# Sheet1.net
KiCad netlist of a schematic drawn in Altium Designer
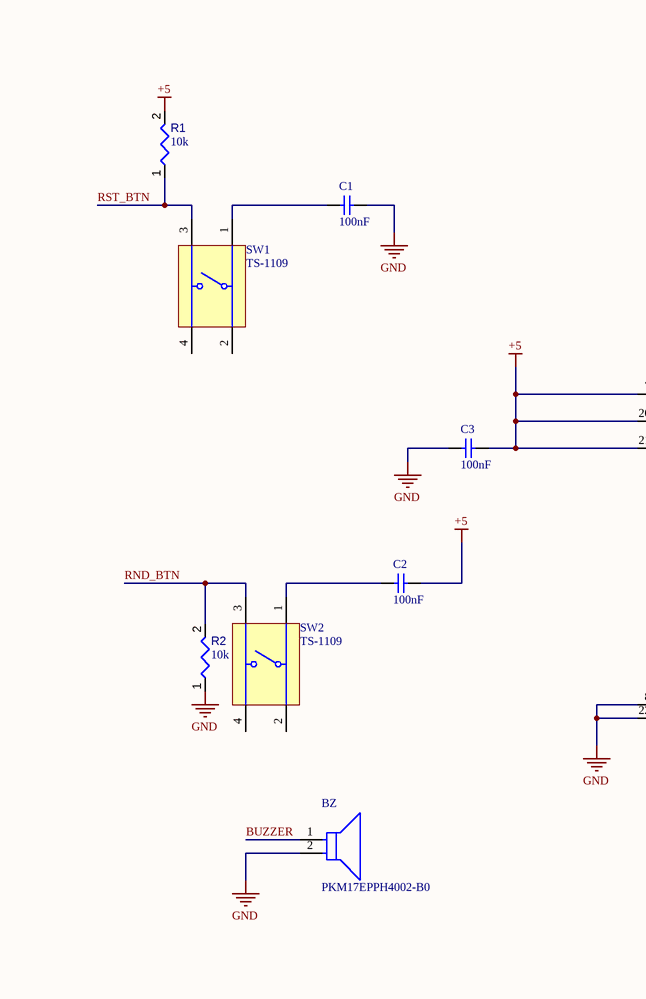
[diagram p0: Sheet1.SchDoc, left]
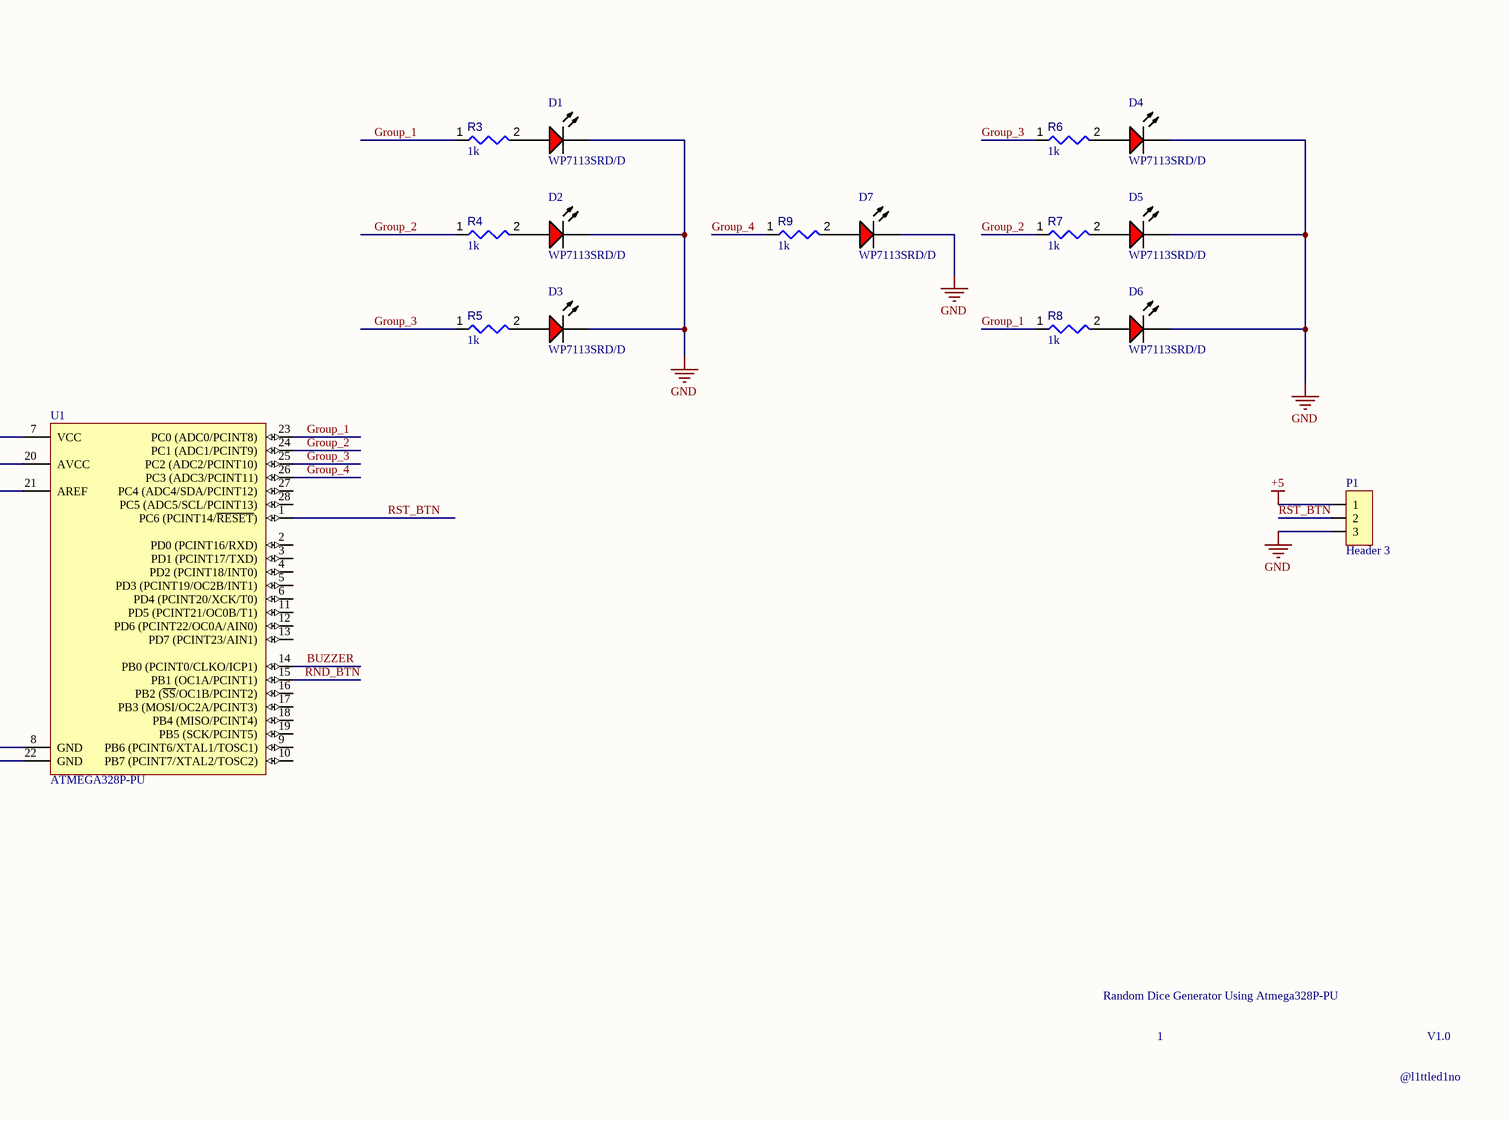
[diagram p1: Sheet1.SchDoc, right]

(export (version "E")
  (design (tool "Eeschema 10.0.6"))
  (components
    (comp (ref "BZ")
      (value "PKM17EPPH4002-B0")
      (footprint "FP-PKM17EPPH4002-B0-MFG")
      (description "AUDIO PIEZO TRANSDUCER 25V TH")
      (libsource (lib "Altium Content Vault") (part "5f581d31613f872430949aa526fd155"))
    )
    (comp (ref "C1")
      (value "100nF")
      (footprint "CAP Ceramic/W200")
      (description "Capacitor non-pol")
      (libsource (lib "chipfc_libs") (part "Capacitor NP"))
    )
    (comp (ref "C2")
      (value "100nF")
      (footprint "CAP Ceramic/W200")
      (description "Capacitor non-pol")
      (libsource (lib "chipfc_libs") (part "Capacitor NP"))
    )
    (comp (ref "C3")
      (value "100nF")
      (footprint "CAP Ceramic/W200")
      (description "Capacitor non-pol")
      (libsource (lib "chipfc_libs") (part "Capacitor NP"))
    )
    (comp (ref "D1")
      (value "WP7113SRD/D")
      (footprint "KING-WP7113SRDD_V")
      (description "The Super Bright Red Source Color Device, 1.85 V, -40 to 85 degC, 2-Pin THD, RoHS, Tape and Reel")
      (fields (field (name "MANUFACTURER") "Kingbright"))
      (libsource (lib "l1ttled1no") (part "LED-RED-AK-2"))
    )
    (comp (ref "D2")
      (value "WP7113SRD/D")
      (footprint "KING-WP7113SRDD_V")
      (description "The Super Bright Red Source Color Device, 1.85 V, -40 to 85 degC, 2-Pin THD, RoHS, Tape and Reel")
      (fields (field (name "MANUFACTURER") "Kingbright"))
      (libsource (lib "l1ttled1no") (part "LED-RED-AK-2"))
    )
    (comp (ref "D3")
      (value "WP7113SRD/D")
      (footprint "KING-WP7113SRDD_V")
      (description "The Super Bright Red Source Color Device, 1.85 V, -40 to 85 degC, 2-Pin THD, RoHS, Tape and Reel")
      (fields (field (name "MANUFACTURER") "Kingbright"))
      (libsource (lib "l1ttled1no") (part "LED-RED-AK-2"))
    )
    (comp (ref "D4")
      (value "WP7113SRD/D")
      (footprint "KING-WP7113SRDD_V")
      (description "The Super Bright Red Source Color Device, 1.85 V, -40 to 85 degC, 2-Pin THD, RoHS, Tape and Reel")
      (fields (field (name "MANUFACTURER") "Kingbright"))
      (libsource (lib "l1ttled1no") (part "LED-RED-AK-2"))
    )
    (comp (ref "D5")
      (value "WP7113SRD/D")
      (footprint "KING-WP7113SRDD_V")
      (description "The Super Bright Red Source Color Device, 1.85 V, -40 to 85 degC, 2-Pin THD, RoHS, Tape and Reel")
      (fields (field (name "MANUFACTURER") "Kingbright"))
      (libsource (lib "l1ttled1no") (part "LED-RED-AK-2"))
    )
    (comp (ref "D6")
      (value "WP7113SRD/D")
      (footprint "KING-WP7113SRDD_V")
      (description "The Super Bright Red Source Color Device, 1.85 V, -40 to 85 degC, 2-Pin THD, RoHS, Tape and Reel")
      (fields (field (name "MANUFACTURER") "Kingbright"))
      (libsource (lib "l1ttled1no") (part "LED-RED-AK-2"))
    )
    (comp (ref "D7")
      (value "WP7113SRD/D")
      (footprint "KING-WP7113SRDD_V")
      (description "The Super Bright Red Source Color Device, 1.85 V, -40 to 85 degC, 2-Pin THD, RoHS, Tape and Reel")
      (fields (field (name "MANUFACTURER") "Kingbright"))
      (libsource (lib "l1ttled1no") (part "LED-RED-AK-2"))
    )
    (comp (ref "P1")
      (value "Header 3")
      (footprint "HDR/Header/3/c1")
      (description "Header, 3-Pin")
      (libsource (lib "connectors") (part "Header 3"))
    )
    (comp (ref "R1")
      (value "10k")
      (footprint "RESA60-630X240")
      (description "Axial Resistor, 10 KOhm, +/- 1%, 0.25 W, -55 to 155 degC, 2-Pin THD, RoHS, Bulk")
      (fields (field (name "TOLERANCE") "1%") (field (name "POWER") "250mW"))
      (libsource (lib "l1ttled1no") (part "RES-2"))
    )
    (comp (ref "R2")
      (value "10k")
      (footprint "RESA60-630X240")
      (description "Axial Resistor, 10 KOhm, +/- 1%, 0.25 W, -55 to 155 degC, 2-Pin THD, RoHS, Bulk")
      (fields (field (name "TOLERANCE") "1%") (field (name "POWER") "250mW"))
      (libsource (lib "l1ttled1no") (part "RES-2"))
    )
    (comp (ref "R3")
      (value "1k")
      (footprint "RESA60-630X240")
      (description "Axial Resistor, 1 KOhm, +/- 1%, 250 mW, -55 to 155 degC, 2-Pin THD, RoHS, Bulk")
      (fields (field (name "TOLERANCE") "1%") (field (name "POWER") "250mW"))
      (libsource (lib "l1ttled1no") (part "RES-2"))
    )
    (comp (ref "R4")
      (value "1k")
      (footprint "RESA60-630X240")
      (description "Axial Resistor, 1 KOhm, +/- 1%, 250 mW, -55 to 155 degC, 2-Pin THD, RoHS, Bulk")
      (fields (field (name "TOLERANCE") "1%") (field (name "POWER") "250mW"))
      (libsource (lib "l1ttled1no") (part "RES-2"))
    )
    (comp (ref "R5")
      (value "1k")
      (footprint "RESA60-630X240")
      (description "Axial Resistor, 1 KOhm, +/- 1%, 250 mW, -55 to 155 degC, 2-Pin THD, RoHS, Bulk")
      (fields (field (name "TOLERANCE") "1%") (field (name "POWER") "250mW"))
      (libsource (lib "l1ttled1no") (part "RES-2"))
    )
    (comp (ref "R6")
      (value "1k")
      (footprint "RESA60-630X240")
      (description "Axial Resistor, 1 KOhm, +/- 1%, 250 mW, -55 to 155 degC, 2-Pin THD, RoHS, Bulk")
      (fields (field (name "TOLERANCE") "1%") (field (name "POWER") "250mW"))
      (libsource (lib "l1ttled1no") (part "RES-2"))
    )
    (comp (ref "R7")
      (value "1k")
      (footprint "RESA60-630X240")
      (description "Axial Resistor, 1 KOhm, +/- 1%, 250 mW, -55 to 155 degC, 2-Pin THD, RoHS, Bulk")
      (fields (field (name "TOLERANCE") "1%") (field (name "POWER") "250mW"))
      (libsource (lib "l1ttled1no") (part "RES-2"))
    )
    (comp (ref "R8")
      (value "1k")
      (footprint "RESA60-630X240")
      (description "Axial Resistor, 1 KOhm, +/- 1%, 250 mW, -55 to 155 degC, 2-Pin THD, RoHS, Bulk")
      (fields (field (name "TOLERANCE") "1%") (field (name "POWER") "250mW"))
      (libsource (lib "l1ttled1no") (part "RES-2"))
    )
    (comp (ref "R9")
      (value "1k")
      (footprint "RESA60-630X240")
      (description "Axial Resistor, 1 KOhm, +/- 1%, 250 mW, -55 to 155 degC, 2-Pin THD, RoHS, Bulk")
      (fields (field (name "TOLERANCE") "1%") (field (name "POWER") "250mW"))
      (libsource (lib "l1ttled1no") (part "RES-2"))
    )
    (comp (ref "SW1")
      (value "TS-1109")
      (footprint "BEST-TS-1109_V")
      (description "Tactile Switch, SPST, 12 V, 50 mA, -20 to 80 degC, 4-Pin THD")
      (fields (field (name "MANUFACTURER") "Shenzhen Best"))
      (libsource (lib "l1ttled1no") (part "SW-SPST-4_A"))
    )
    (comp (ref "SW2")
      (value "TS-1109")
      (footprint "BEST-TS-1109_V")
      (description "Tactile Switch, SPST, 12 V, 50 mA, -20 to 80 degC, 4-Pin THD")
      (fields (field (name "MANUFACTURER") "Shenzhen Best"))
      (libsource (lib "l1ttled1no") (part "SW-SPST-4_A"))
    )
    (comp (ref "U1")
      (value "ATMEGA328P-PU")
      (footprint "ATML-28P3")
      (fields (field (name "MANUFACTURER") "Atmel"))
      (libsource (lib "l1ttled1no") (part "MC-8B-ATM48-IL28"))
    )
  )
  (nets
    (net (code "1") (name "+5") (class "Default")
      (node (ref "C2") (pin "2") (pinfunction "2_2") (pintype "passive"))
      (node (ref "C3") (pin "2") (pinfunction "2_2") (pintype "passive"))
      (node (ref "P1") (pin "1") (pinfunction "1_1") (pintype "passive"))
      (node (ref "R1") (pin "2") (pinfunction "2_2") (pintype "passive"))
      (node (ref "U1") (pin "20") (pinfunction "AVCC_20") (pintype "power_in"))
      (node (ref "U1") (pin "21") (pinfunction "AREF_21") (pintype "power_in"))
      (node (ref "U1") (pin "7") (pinfunction "VCC_7") (pintype "power_in"))
    )
    (net (code "2") (name "/BUZZER") (class "Default")
      (node (ref "BZ") (pin "1") (pinfunction "1_1") (pintype "passive"))
      (node (ref "U1") (pin "14") (pinfunction "PB0_(PCINT0/CLKO/ICP1)_14") (pintype "bidirectional"))
    )
    (net (code "3") (name "/Group_1") (class "Default")
      (node (ref "R3") (pin "1") (pinfunction "1_1") (pintype "passive"))
      (node (ref "R8") (pin "1") (pinfunction "1_1") (pintype "passive"))
      (node (ref "U1") (pin "23") (pinfunction "PC0_(ADC0/PCINT8)_23") (pintype "bidirectional"))
    )
    (net (code "4") (name "/Group_2") (class "Default")
      (node (ref "R4") (pin "1") (pinfunction "1_1") (pintype "passive"))
      (node (ref "R7") (pin "1") (pinfunction "1_1") (pintype "passive"))
      (node (ref "U1") (pin "24") (pinfunction "PC1_(ADC1/PCINT9)_24") (pintype "bidirectional"))
    )
    (net (code "5") (name "/Group_3") (class "Default")
      (node (ref "R5") (pin "1") (pinfunction "1_1") (pintype "passive"))
      (node (ref "R6") (pin "1") (pinfunction "1_1") (pintype "passive"))
      (node (ref "U1") (pin "25") (pinfunction "PC2_(ADC2/PCINT10)_25") (pintype "bidirectional"))
    )
    (net (code "6") (name "/Group_4") (class "Default")
      (node (ref "R9") (pin "1") (pinfunction "1_1") (pintype "passive"))
      (node (ref "U1") (pin "26") (pinfunction "PC3_(ADC3/PCINT11)_26") (pintype "bidirectional"))
    )
    (net (code "7") (name "/RND_BTN") (class "Default")
      (node (ref "R2") (pin "2") (pinfunction "2_2") (pintype "passive"))
      (node (ref "SW2") (pin "3") (pinfunction "3_3") (pintype "passive"))
      (node (ref "U1") (pin "15") (pinfunction "PB1_(OC1A/PCINT1)_15") (pintype "bidirectional"))
    )
    (net (code "8") (name "/RST_BTN") (class "Default")
      (node (ref "P1") (pin "2") (pinfunction "2_2") (pintype "passive"))
      (node (ref "R1") (pin "1") (pinfunction "1_1") (pintype "passive"))
      (node (ref "SW1") (pin "3") (pinfunction "3_3") (pintype "passive"))
      (node (ref "U1") (pin "1") (pinfunction "PC6_(PCINT14/~{RESET})_1") (pintype "bidirectional"))
    )
    (net (code "9") (name "GND") (class "Default")
      (node (ref "BZ") (pin "2") (pinfunction "2_2") (pintype "passive"))
      (node (ref "C1") (pin "2") (pinfunction "2_2") (pintype "passive"))
      (node (ref "C3") (pin "1") (pinfunction "1_1") (pintype "passive"))
      (node (ref "D1") (pin "2") (pinfunction "K_2") (pintype "passive"))
      (node (ref "D2") (pin "2") (pinfunction "K_2") (pintype "passive"))
      (node (ref "D3") (pin "2") (pinfunction "K_2") (pintype "passive"))
      (node (ref "D4") (pin "2") (pinfunction "K_2") (pintype "passive"))
      (node (ref "D5") (pin "2") (pinfunction "K_2") (pintype "passive"))
      (node (ref "D6") (pin "2") (pinfunction "K_2") (pintype "passive"))
      (node (ref "D7") (pin "2") (pinfunction "K_2") (pintype "passive"))
      (node (ref "P1") (pin "3") (pinfunction "3_3") (pintype "passive"))
      (node (ref "R2") (pin "1") (pinfunction "1_1") (pintype "passive"))
      (node (ref "U1") (pin "22") (pinfunction "GND_22") (pintype "power_in"))
      (node (ref "U1") (pin "8") (pinfunction "GND_8") (pintype "power_in"))
    )
    (net (code "10") (name "Net-(C1-Pad1)") (class "Default")
      (node (ref "C1") (pin "1") (pinfunction "1_1") (pintype "passive"))
      (node (ref "SW1") (pin "1") (pinfunction "1_1") (pintype "passive"))
    )
    (net (code "11") (name "Net-(C2-Pad1)") (class "Default")
      (node (ref "C2") (pin "1") (pinfunction "1_1") (pintype "passive"))
      (node (ref "SW2") (pin "1") (pinfunction "1_1") (pintype "passive"))
    )
    (net (code "12") (name "Net-(D1-A)") (class "Default")
      (node (ref "D1") (pin "1") (pinfunction "A_1") (pintype "passive"))
      (node (ref "R3") (pin "2") (pinfunction "2_2") (pintype "passive"))
    )
    (net (code "13") (name "Net-(D2-A)") (class "Default")
      (node (ref "D2") (pin "1") (pinfunction "A_1") (pintype "passive"))
      (node (ref "R4") (pin "2") (pinfunction "2_2") (pintype "passive"))
    )
    (net (code "14") (name "Net-(D3-A)") (class "Default")
      (node (ref "D3") (pin "1") (pinfunction "A_1") (pintype "passive"))
      (node (ref "R5") (pin "2") (pinfunction "2_2") (pintype "passive"))
    )
    (net (code "15") (name "Net-(D4-A)") (class "Default")
      (node (ref "D4") (pin "1") (pinfunction "A_1") (pintype "passive"))
      (node (ref "R6") (pin "2") (pinfunction "2_2") (pintype "passive"))
    )
    (net (code "16") (name "Net-(D5-A)") (class "Default")
      (node (ref "D5") (pin "1") (pinfunction "A_1") (pintype "passive"))
      (node (ref "R7") (pin "2") (pinfunction "2_2") (pintype "passive"))
    )
    (net (code "17") (name "Net-(D6-A)") (class "Default")
      (node (ref "D6") (pin "1") (pinfunction "A_1") (pintype "passive"))
      (node (ref "R8") (pin "2") (pinfunction "2_2") (pintype "passive"))
    )
    (net (code "18") (name "Net-(D7-A)") (class "Default")
      (node (ref "D7") (pin "1") (pinfunction "A_1") (pintype "passive"))
      (node (ref "R9") (pin "2") (pinfunction "2_2") (pintype "passive"))
    )
    (net (code "19") (name "unconnected-(SW1-Pad2)") (class "Default")
      (node (ref "SW1") (pin "2") (pinfunction "2_2") (pintype "passive"))
    )
    (net (code "20") (name "unconnected-(SW1-Pad4)") (class "Default")
      (node (ref "SW1") (pin "4") (pinfunction "4_4") (pintype "passive"))
    )
    (net (code "21") (name "unconnected-(SW2-Pad2)") (class "Default")
      (node (ref "SW2") (pin "2") (pinfunction "2_2") (pintype "passive"))
    )
    (net (code "22") (name "unconnected-(SW2-Pad4)") (class "Default")
      (node (ref "SW2") (pin "4") (pinfunction "4_4") (pintype "passive"))
    )
    (net (code "23") (name "unconnected-(U1-PB2_(~{SS}{slash}OC1B{slash}PCINT2)-Pad16)") (class "Default")
      (node (ref "U1") (pin "16") (pinfunction "PB2_(~{SS}/OC1B/PCINT2)_16") (pintype "bidirectional"))
    )
    (net (code "24") (name "unconnected-(U1-PB3_(MOSI{slash}OC2A{slash}PCINT3)-Pad17)") (class "Default")
      (node (ref "U1") (pin "17") (pinfunction "PB3_(MOSI/OC2A/PCINT3)_17") (pintype "bidirectional"))
    )
    (net (code "25") (name "unconnected-(U1-PB4_(MISO{slash}PCINT4)-Pad18)") (class "Default")
      (node (ref "U1") (pin "18") (pinfunction "PB4_(MISO/PCINT4)_18") (pintype "bidirectional"))
    )
    (net (code "26") (name "unconnected-(U1-PB5_(SCK{slash}PCINT5)-Pad19)") (class "Default")
      (node (ref "U1") (pin "19") (pinfunction "PB5_(SCK/PCINT5)_19") (pintype "bidirectional"))
    )
    (net (code "27") (name "unconnected-(U1-PB6_(PCINT6{slash}XTAL1{slash}TOSC1)-Pad9)") (class "Default")
      (node (ref "U1") (pin "9") (pinfunction "PB6_(PCINT6/XTAL1/TOSC1)_9") (pintype "bidirectional"))
    )
    (net (code "28") (name "unconnected-(U1-PB7_(PCINT7{slash}XTAL2{slash}TOSC2)-Pad10)") (class "Default")
      (node (ref "U1") (pin "10") (pinfunction "PB7_(PCINT7/XTAL2/TOSC2)_10") (pintype "bidirectional"))
    )
    (net (code "29") (name "unconnected-(U1-PC4_(ADC4{slash}SDA{slash}PCINT12)-Pad27)") (class "Default")
      (node (ref "U1") (pin "27") (pinfunction "PC4_(ADC4/SDA/PCINT12)_27") (pintype "bidirectional"))
    )
    (net (code "30") (name "unconnected-(U1-PC5_(ADC5{slash}SCL{slash}PCINT13)-Pad28)") (class "Default")
      (node (ref "U1") (pin "28") (pinfunction "PC5_(ADC5/SCL/PCINT13)_28") (pintype "bidirectional"))
    )
    (net (code "31") (name "unconnected-(U1-PD0_(PCINT16{slash}RXD)-Pad2)") (class "Default")
      (node (ref "U1") (pin "2") (pinfunction "PD0_(PCINT16/RXD)_2") (pintype "bidirectional"))
    )
    (net (code "32") (name "unconnected-(U1-PD1_(PCINT17{slash}TXD)-Pad3)") (class "Default")
      (node (ref "U1") (pin "3") (pinfunction "PD1_(PCINT17/TXD)_3") (pintype "bidirectional"))
    )
    (net (code "33") (name "unconnected-(U1-PD2_(PCINT18{slash}INT0)-Pad4)") (class "Default")
      (node (ref "U1") (pin "4") (pinfunction "PD2_(PCINT18/INT0)_4") (pintype "bidirectional"))
    )
    (net (code "34") (name "unconnected-(U1-PD3_(PCINT19{slash}OC2B{slash}INT1)-Pad5)") (class "Default")
      (node (ref "U1") (pin "5") (pinfunction "PD3_(PCINT19/OC2B/INT1)_5") (pintype "bidirectional"))
    )
    (net (code "35") (name "unconnected-(U1-PD4_(PCINT20{slash}XCK{slash}T0)-Pad6)") (class "Default")
      (node (ref "U1") (pin "6") (pinfunction "PD4_(PCINT20/XCK/T0)_6") (pintype "bidirectional"))
    )
    (net (code "36") (name "unconnected-(U1-PD5_(PCINT21{slash}OC0B{slash}T1)-Pad11)") (class "Default")
      (node (ref "U1") (pin "11") (pinfunction "PD5_(PCINT21/OC0B/T1)_11") (pintype "bidirectional"))
    )
    (net (code "37") (name "unconnected-(U1-PD6_(PCINT22{slash}OC0A{slash}AIN0)-Pad12)") (class "Default")
      (node (ref "U1") (pin "12") (pinfunction "PD6_(PCINT22/OC0A/AIN0)_12") (pintype "bidirectional"))
    )
    (net (code "38") (name "unconnected-(U1-PD7_(PCINT23{slash}AIN1)-Pad13)") (class "Default")
      (node (ref "U1") (pin "13") (pinfunction "PD7_(PCINT23/AIN1)_13") (pintype "bidirectional"))
    )
  )
)
